# SparkFun_MEMs_Microphone_Breakout_ICS-40.net
KiCad netlist of a schematic drawn in EAGLE
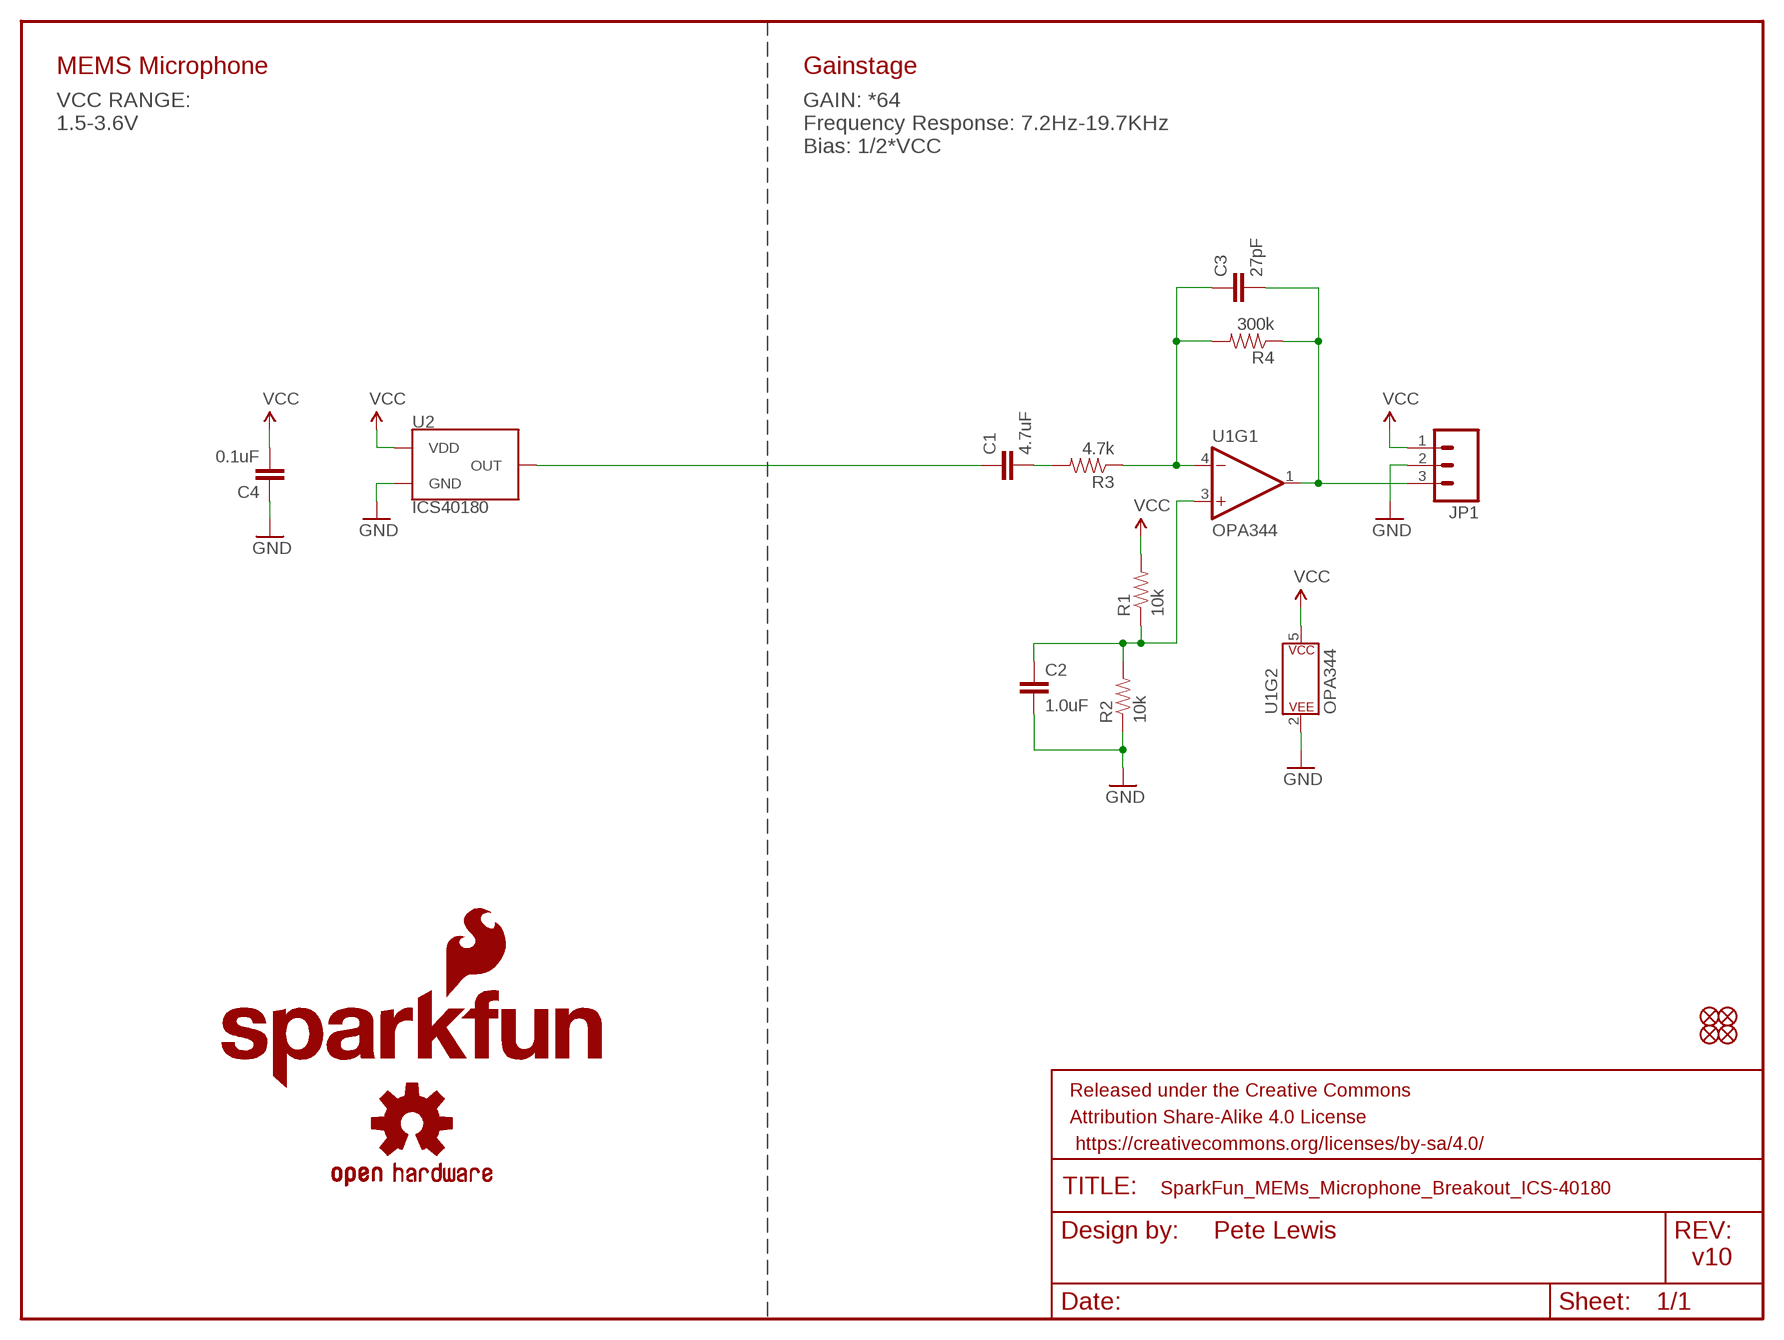
[diagram p0: schematic, sheet 1]

(export (version "E")
  (design (tool "Eeschema 10.0.6"))
  (components
    (comp (ref "C1")
      (value "4.7uF")
      (footprint "eagle-import:0603")
      (libsource (lib "eagle-import") (part "4.7UF-0603-6.3V-(10%)"))
    )
    (comp (ref "C2")
      (value "1.0uF")
      (footprint "eagle-import:0603")
      (libsource (lib "eagle-import") (part "1.0UF-0603-16V-10%"))
    )
    (comp (ref "C3")
      (value "27pF")
      (footprint "eagle-import:0603")
      (libsource (lib "eagle-import") (part "27PF-0603-50V-5%"))
    )
    (comp (ref "C4")
      (value "0.1uF")
      (footprint "eagle-import:0603")
      (libsource (lib "eagle-import") (part "0.1UF-0603-25V-(+80/-20%)"))
    )
    (comp (ref "FD1")
      (value "FIDUCIALUFIDUCIAL")
      (footprint "eagle-import:FIDUCIAL-MICRO")
      (libsource (lib "eagle-import") (part "FIDUCIALUFIDUCIAL"))
    )
    (comp (ref "FD2")
      (value "FIDUCIALUFIDUCIAL")
      (footprint "eagle-import:FIDUCIAL-MICRO")
      (libsource (lib "eagle-import") (part "FIDUCIALUFIDUCIAL"))
    )
    (comp (ref "FD3")
      (value "FIDUCIALUFIDUCIAL")
      (footprint "eagle-import:FIDUCIAL-MICRO")
      (libsource (lib "eagle-import") (part "FIDUCIALUFIDUCIAL"))
    )
    (comp (ref "FD4")
      (value "FIDUCIALUFIDUCIAL")
      (footprint "eagle-import:FIDUCIAL-MICRO")
      (libsource (lib "eagle-import") (part "FIDUCIALUFIDUCIAL"))
    )
    (comp (ref "FRAME2")
      (value "FRAME-LETTER")
      (footprint "eagle-import:CREATIVE_COMMONS")
      (libsource (lib "eagle-import") (part "FRAME-LETTER"))
    )
    (comp (ref "JP1")
      (value "CONN_031X03_NO_SILK")
      (footprint "eagle-import:1X03_NO_SILK")
      (libsource (lib "eagle-import") (part "CONN_031X03_NO_SILK"))
    )
    (comp (ref "LOGO1")
      (value "SFE_LOGO_FLAME.1_INCH")
      (footprint "eagle-import:SFE_LOGO_FLAME_.1")
      (libsource (lib "eagle-import") (part "SFE_LOGO_FLAME.1_INCH"))
    )
    (comp (ref "LOGO2")
      (value "OSHW-LOGOMINI")
      (footprint "eagle-import:OSHW-LOGO-MINI")
      (libsource (lib "eagle-import") (part "OSHW-LOGOMINI"))
    )
    (comp (ref "R1")
      (value "10k")
      (footprint "eagle-import:0603")
      (libsource (lib "eagle-import") (part "10KOHM-0603-1/10W-1%"))
    )
    (comp (ref "R2")
      (value "10k")
      (footprint "eagle-import:0603")
      (libsource (lib "eagle-import") (part "10KOHM-0603-1/10W-1%"))
    )
    (comp (ref "R3")
      (value "4.7k")
      (footprint "eagle-import:0603")
      (libsource (lib "eagle-import") (part "4.7KOHM-0603-1/10W-1%"))
    )
    (comp (ref "R4")
      (value "300k")
      (footprint "eagle-import:0603")
      (libsource (lib "eagle-import") (part "300KOHM-0603-1/10W-1%"))
    )
    (comp (ref "U1")
      (value "OPA344")
      (footprint "eagle-import:SOT23-5")
      (libsource (lib "eagle-import") (part "OPA344"))
    )
    (comp (ref "U2")
      (value "ICS40180")
      (footprint "eagle-import:ICS40180")
      (libsource (lib "eagle-import") (part "ICS40180"))
    )
  )
  (nets
    (net (code "1") (name "GND") (class "Default")
      (node (ref "C2") (pin "2") (pinfunction "2_2") (pintype "passive"))
      (node (ref "C4") (pin "1") (pinfunction "1_1") (pintype "passive"))
      (node (ref "JP1") (pin "2") (pinfunction "2_2") (pintype "passive"))
      (node (ref "R2") (pin "1") (pinfunction "1_1") (pintype "passive"))
      (node (ref "U1") (pin "2") (pinfunction "P$V-_2") (pintype "bidirectional"))
      (node (ref "U2") (pin "2") (pinfunction "GND_2") (pintype "bidirectional"))
      (node (ref "U2") (pin "3") (pinfunction "GND_3") (pintype "bidirectional"))
      (node (ref "U2") (pin "4") (pinfunction "GND_4") (pintype "bidirectional"))
    )
    (net (code "2") (name "Net-(C1-Pad2)") (class "Default")
      (node (ref "C1") (pin "2") (pinfunction "2_2") (pintype "passive"))
      (node (ref "R3") (pin "2") (pinfunction "2_2") (pintype "passive"))
    )
    (net (code "3") (name "Net-(U1A-+IN)") (class "Default")
      (node (ref "C2") (pin "1") (pinfunction "1_1") (pintype "passive"))
      (node (ref "R1") (pin "1") (pinfunction "1_1") (pintype "passive"))
      (node (ref "R2") (pin "2") (pinfunction "2_2") (pintype "passive"))
      (node (ref "U1") (pin "3") (pinfunction "+IN_3") (pintype "input"))
    )
    (net (code "4") (name "Net-(U1A--IN)") (class "Default")
      (node (ref "C3") (pin "1") (pinfunction "1_1") (pintype "passive"))
      (node (ref "R3") (pin "1") (pinfunction "1_1") (pintype "passive"))
      (node (ref "R4") (pin "2") (pinfunction "2_2") (pintype "passive"))
      (node (ref "U1") (pin "4") (pinfunction "-IN_4") (pintype "input"))
    )
    (net (code "5") (name "Net-(U1A-OUT)") (class "Default")
      (node (ref "C3") (pin "2") (pinfunction "2_2") (pintype "passive"))
      (node (ref "JP1") (pin "3") (pinfunction "3_3") (pintype "passive"))
      (node (ref "R4") (pin "1") (pinfunction "1_1") (pintype "passive"))
      (node (ref "U1") (pin "1") (pinfunction "OUT_1") (pintype "output"))
    )
    (net (code "6") (name "Net-(U2-OUT)") (class "Default")
      (node (ref "C1") (pin "1") (pinfunction "1_1") (pintype "passive"))
      (node (ref "U2") (pin "1") (pinfunction "OUT_1") (pintype "bidirectional"))
    )
    (net (code "7") (name "VCC") (class "Default")
      (node (ref "C4") (pin "2") (pinfunction "2_2") (pintype "passive"))
      (node (ref "JP1") (pin "1") (pinfunction "1_1") (pintype "passive"))
      (node (ref "R1") (pin "2") (pinfunction "2_2") (pintype "passive"))
      (node (ref "U1") (pin "5") (pinfunction "P$V+_5") (pintype "bidirectional"))
      (node (ref "U2") (pin "5") (pinfunction "VDD_5") (pintype "bidirectional"))
    )
  )
)
